# SparkFun_GPS_NEO_M9N_SMA.net
KiCad netlist of a schematic drawn in EAGLE
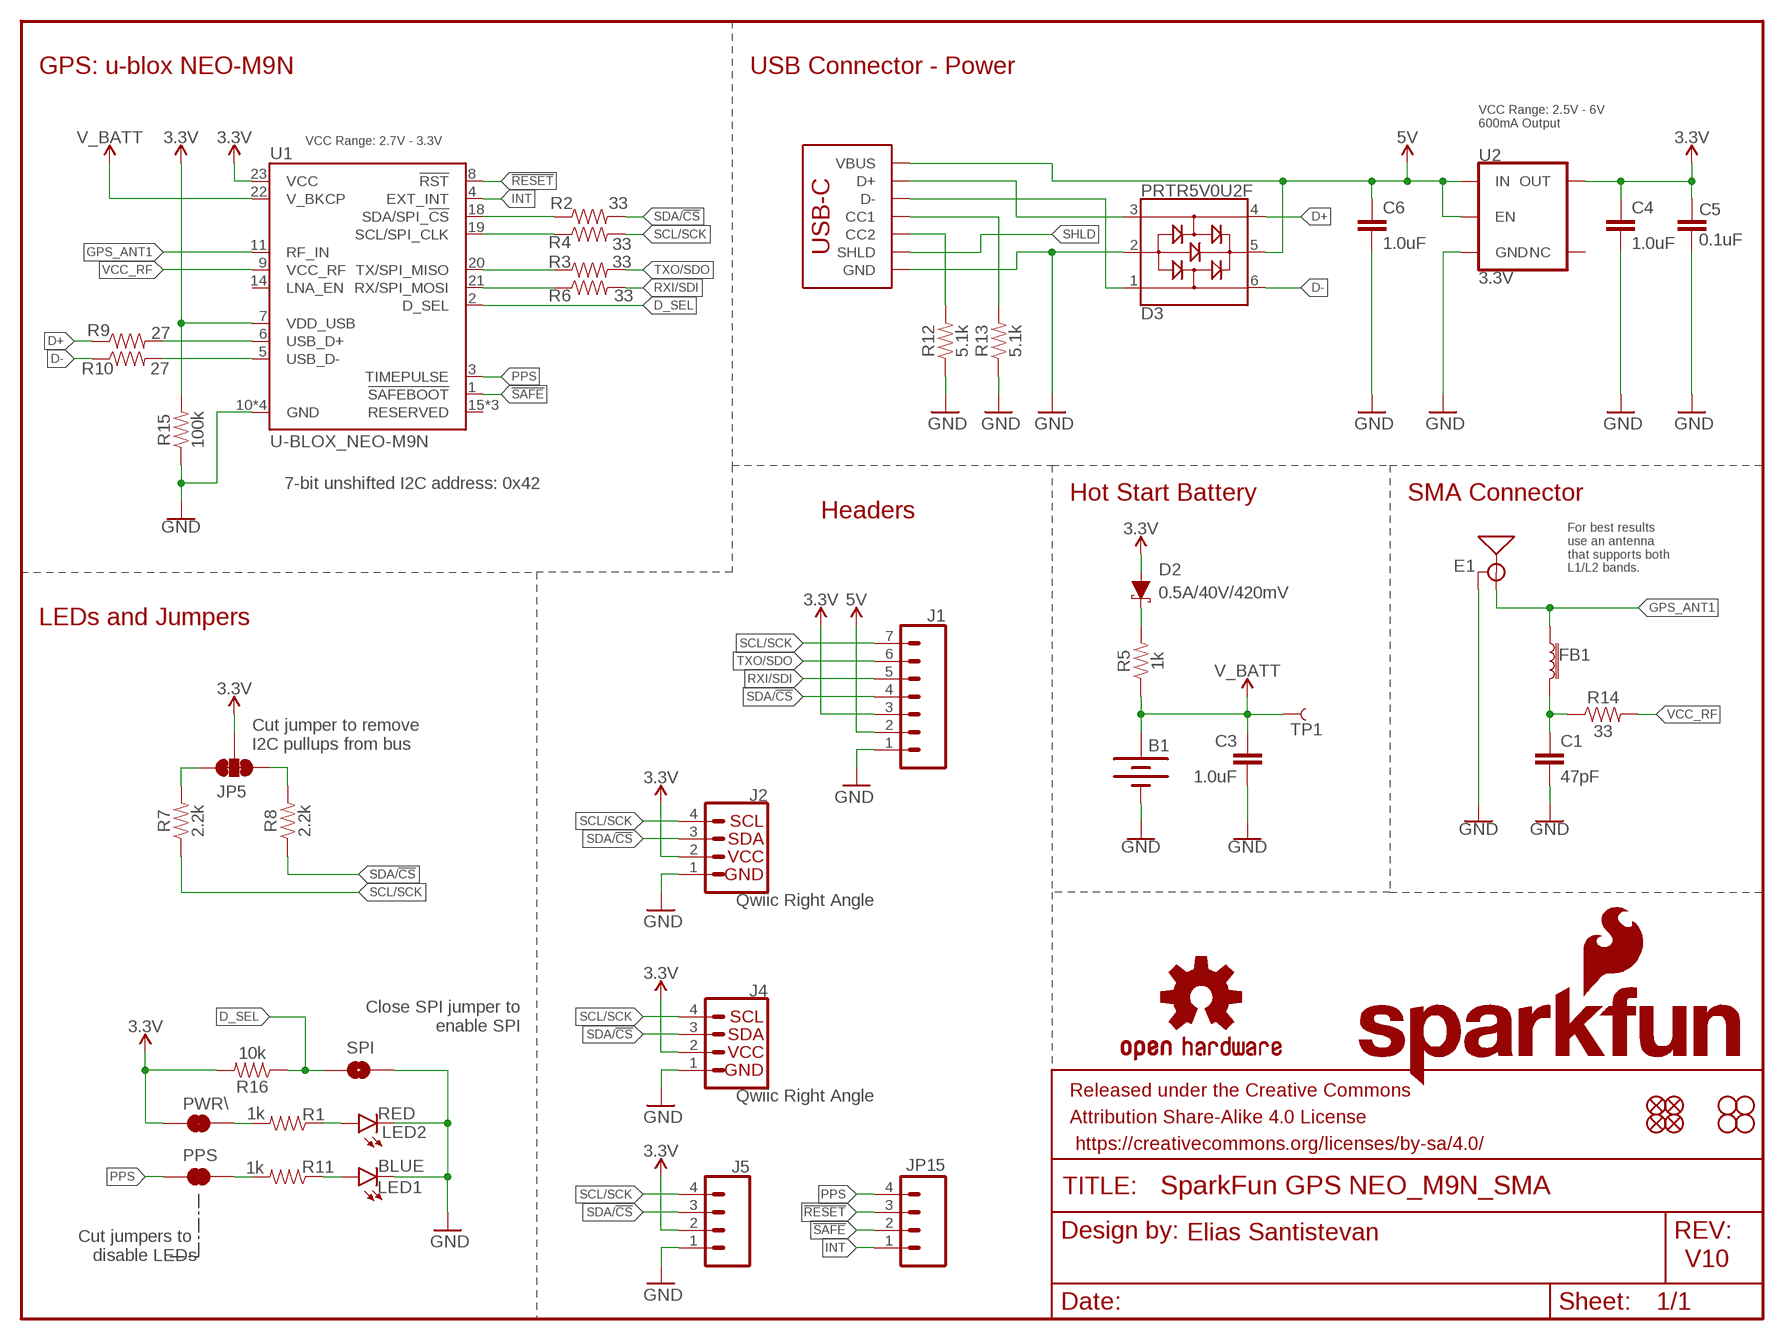
[diagram p0: schematic, sheet 1]

(export (version "E")
  (design (tool "Eeschema 10.0.6"))
  (components
    (comp (ref "B1")
      (value "6.8MM_COIN_CELL")
      (footprint "eagle-import:ML414H_IV01E")
      (libsource (lib "eagle-import") (part "ML414H_IV01E_BATTERY"))
    )
    (comp (ref "C1")
      (value "47pF")
      (footprint "eagle-import:0402")
      (libsource (lib "eagle-import") (part "47PF-0402-25V-5%-X7R"))
    )
    (comp (ref "C3")
      (value "1.0uF")
      (footprint "eagle-import:0603")
      (libsource (lib "eagle-import") (part "1.0UF-0603-16V-10%"))
    )
    (comp (ref "C4")
      (value "1.0uF")
      (footprint "eagle-import:0603")
      (libsource (lib "eagle-import") (part "1.0UF-0603-16V-10%"))
    )
    (comp (ref "C5")
      (value "0.1uF")
      (footprint "eagle-import:0603")
      (libsource (lib "eagle-import") (part "0.1UF-0603-25V-(+80/-20%)"))
    )
    (comp (ref "C6")
      (value "1.0uF")
      (footprint "eagle-import:0603")
      (libsource (lib "eagle-import") (part "1.0UF-0603-16V-10%"))
    )
    (comp (ref "D2")
      (value "0.5A/40V/420mV")
      (footprint "eagle-import:SOD-323")
      (libsource (lib "eagle-import") (part "DIODE-SCHOTTKY-PMEG4005EJ"))
    )
    (comp (ref "D3")
      (value "PRTR5V0U2F")
      (footprint "eagle-import:SOT886")
      (libsource (lib "eagle-import") (part "PRTR5V0U2F"))
    )
    (comp (ref "E1")
      (value "ANTENNA-GROUNDEDEDGE_SMA_SMD")
      (footprint "eagle-import:SMA-EDGE-SMD")
      (libsource (lib "eagle-import") (part "ANTENNA-GROUNDEDEDGE_SMA_SMD"))
    )
    (comp (ref "FB1")
      (value "FERRITE_BEAD-120_OHM-0402")
      (footprint "eagle-import:0402")
      (fields (field (name "MFG_PART") "BLM15HB121SN1D"))
      (libsource (lib "eagle-import") (part "FERRITE_BEAD-120_OHM-0402"))
    )
    (comp (ref "FRAME1")
      (value "FRAME-LETTER")
      (footprint "eagle-import:CREATIVE_COMMONS")
      (libsource (lib "eagle-import") (part "FRAME-LETTER"))
    )
    (comp (ref "J1")
      (value "CONN_07NO_SILK")
      (footprint "eagle-import:1X07_NO_SILK")
      (libsource (lib "eagle-import") (part "CONN_07NO_SILK"))
    )
    (comp (ref "J2")
      (value "Qwiic Right Angle")
      (footprint "eagle-import:JST04_1MM_RA")
      (libsource (lib "eagle-import") (part "I2C_STANDARDQWIIC"))
    )
    (comp (ref "J3")
      (value "USB_C_2-LAYER_PADS")
      (footprint "eagle-import:USB-C-16P-2LAYER-PADS")
      (libsource (lib "eagle-import") (part "USB_C_2-LAYER_PADS"))
    )
    (comp (ref "J4")
      (value "Qwiic Right Angle")
      (footprint "eagle-import:JST04_1MM_RA")
      (libsource (lib "eagle-import") (part "I2C_STANDARDQWIIC"))
    )
    (comp (ref "J5")
      (value "CONN_041X04_NO_SILK_NO_POP")
      (footprint "eagle-import:1X04_NO_SILK")
      (libsource (lib "eagle-import") (part "CONN_041X04_NO_SILK_NO_POP"))
    )
    (comp (ref "JP1")
      (value "STAND-OFF")
      (footprint "eagle-import:STAND-OFF")
      (libsource (lib "eagle-import") (part "STAND-OFF"))
    )
    (comp (ref "JP5")
      (value "JUMPER-SMT_3_2-NC_TRACE_SILK")
      (footprint "eagle-import:SMT-JUMPER_3_2-NC_TRACE_SILK")
      (libsource (lib "eagle-import") (part "JUMPER-SMT_3_2-NC_TRACE_SILK"))
    )
    (comp (ref "JP15")
      (value "CONN_041X04_NO_SILK_NO_POP")
      (footprint "eagle-import:1X04_NO_SILK")
      (libsource (lib "eagle-import") (part "CONN_041X04_NO_SILK_NO_POP"))
    )
    (comp (ref "JP21")
      (value "FIDUCIALUFIDUCIAL")
      (footprint "eagle-import:MICRO-FIDUCIAL")
      (libsource (lib "eagle-import") (part "FIDUCIALUFIDUCIAL"))
    )
    (comp (ref "JP31")
      (value "STAND-OFF")
      (footprint "eagle-import:STAND-OFF")
      (libsource (lib "eagle-import") (part "STAND-OFF"))
    )
    (comp (ref "JP61")
      (value "FIDUCIALUFIDUCIAL")
      (footprint "eagle-import:MICRO-FIDUCIAL")
      (libsource (lib "eagle-import") (part "FIDUCIALUFIDUCIAL"))
    )
    (comp (ref "JP71")
      (value "FIDUCIALUFIDUCIAL")
      (footprint "eagle-import:MICRO-FIDUCIAL")
      (libsource (lib "eagle-import") (part "FIDUCIALUFIDUCIAL"))
    )
    (comp (ref "JP81")
      (value "FIDUCIALUFIDUCIAL")
      (footprint "eagle-import:MICRO-FIDUCIAL")
      (libsource (lib "eagle-import") (part "FIDUCIALUFIDUCIAL"))
    )
    (comp (ref "JP91")
      (value "STAND-OFF")
      (footprint "eagle-import:STAND-OFF")
      (libsource (lib "eagle-import") (part "STAND-OFF"))
    )
    (comp (ref "JP101")
      (value "STAND-OFF")
      (footprint "eagle-import:STAND-OFF")
      (libsource (lib "eagle-import") (part "STAND-OFF"))
    )
    (comp (ref "LED1")
      (value "BLUE")
      (footprint "eagle-import:LED-0603")
      (libsource (lib "eagle-import") (part "LED-BLUE0603"))
    )
    (comp (ref "LED2")
      (value "RED")
      (footprint "eagle-import:LED-0603")
      (libsource (lib "eagle-import") (part "LED-RED0603"))
    )
    (comp (ref "LOGO1")
      (value "OSHW-LOGOMINI")
      (footprint "eagle-import:OSHW-LOGO-MINI")
      (libsource (lib "eagle-import") (part "OSHW-LOGOMINI"))
    )
    (comp (ref "LOGO2")
      (value "SFE_LOGO_NAME_FLAME.1_INCH")
      (footprint "eagle-import:SFE_LOGO_NAME_FLAME_.1")
      (libsource (lib "eagle-import") (part "SFE_LOGO_NAME_FLAME.1_INCH"))
    )
    (comp (ref "PPS")
      (value "JUMPER-SMT_2_NC_TRACE_SILK")
      (footprint "eagle-import:SMT-JUMPER_2_NC_TRACE_SILK")
      (libsource (lib "eagle-import") (part "JUMPER-SMT_2_NC_TRACE_SILK"))
    )
    (comp (ref "PWR\\")
      (value "JUMPER-SMT_2_NC_TRACE_SILK")
      (footprint "eagle-import:SMT-JUMPER_2_NC_TRACE_SILK")
      (libsource (lib "eagle-import") (part "JUMPER-SMT_2_NC_TRACE_SILK"))
    )
    (comp (ref "R1")
      (value "1k")
      (footprint "eagle-import:0603")
      (libsource (lib "eagle-import") (part "1KOHM-0603-1/10W-1%"))
    )
    (comp (ref "R2")
      (value "33")
      (footprint "eagle-import:0603")
      (libsource (lib "eagle-import") (part "33OHM-0603-1/10W-1%"))
    )
    (comp (ref "R3")
      (value "33")
      (footprint "eagle-import:0603")
      (libsource (lib "eagle-import") (part "33OHM-0603-1/10W-1%"))
    )
    (comp (ref "R4")
      (value "33")
      (footprint "eagle-import:0603")
      (libsource (lib "eagle-import") (part "33OHM-0603-1/10W-1%"))
    )
    (comp (ref "R5")
      (value "1k")
      (footprint "eagle-import:0603")
      (libsource (lib "eagle-import") (part "1KOHM-0603-1/10W-1%"))
    )
    (comp (ref "R6")
      (value "33")
      (footprint "eagle-import:0603")
      (libsource (lib "eagle-import") (part "33OHM-0603-1/10W-1%"))
    )
    (comp (ref "R7")
      (value "2.2k")
      (footprint "eagle-import:0603")
      (libsource (lib "eagle-import") (part "2.2KOHM-0603-1/10W-1%"))
    )
    (comp (ref "R8")
      (value "2.2k")
      (footprint "eagle-import:0603")
      (libsource (lib "eagle-import") (part "2.2KOHM-0603-1/10W-1%"))
    )
    (comp (ref "R9")
      (value "27")
      (footprint "eagle-import:0603")
      (libsource (lib "eagle-import") (part "27OHM-0603-1/10W-1%"))
    )
    (comp (ref "R10")
      (value "27")
      (footprint "eagle-import:0603")
      (libsource (lib "eagle-import") (part "27OHM-0603-1/10W-1%"))
    )
    (comp (ref "R11")
      (value "1k")
      (footprint "eagle-import:0603")
      (libsource (lib "eagle-import") (part "1KOHM-0603-1/10W-1%"))
    )
    (comp (ref "R12")
      (value "5.1k")
      (footprint "eagle-import:0603")
      (libsource (lib "eagle-import") (part "5.1KOHM5.1KOHM-0603-1/10W-1%"))
    )
    (comp (ref "R13")
      (value "5.1k")
      (footprint "eagle-import:0603")
      (libsource (lib "eagle-import") (part "5.1KOHM5.1KOHM-0603-1/10W-1%"))
    )
    (comp (ref "R14")
      (value "33")
      (footprint "eagle-import:0402")
      (libsource (lib "eagle-import") (part "33OHM-0402-1/10W-1%"))
    )
    (comp (ref "R15")
      (value "100k")
      (footprint "eagle-import:0603")
      (libsource (lib "eagle-import") (part "100KOHM-0603-1/10W-1%"))
    )
    (comp (ref "R16")
      (value "10k")
      (footprint "eagle-import:0402")
      (libsource (lib "eagle-import") (part "10KOHM-0402-1/16W-1%"))
    )
    (comp (ref "SPI")
      (value "JUMPER-SMT_2_NO_SILK")
      (footprint "eagle-import:SMT-JUMPER_2_NO_SILK")
      (libsource (lib "eagle-import") (part "JUMPER-SMT_2_NO_SILK"))
    )
    (comp (ref "TP1")
      (value "TEST-POINT3X4")
      (footprint "eagle-import:PAD.03X.04")
      (libsource (lib "eagle-import") (part "TEST-POINT3X4"))
    )
    (comp (ref "U1")
      (value "U-BLOX_NEO-M9N")
      (footprint "eagle-import:NEO-M9N_M8T_M8U")
      (libsource (lib "eagle-import") (part "U-BLOX_NEO-M9N"))
    )
    (comp (ref "U2")
      (value "3.3V")
      (footprint "eagle-import:SOT23-5")
      (libsource (lib "eagle-import") (part "V_REG_AP2112K-3.3V"))
    )
  )
  (nets
    (net (code "1") (name "/SDA{slash}~{CS}") (class "Default")
      (node (ref "J1") (pin "4") (pinfunction "4_4") (pintype "passive"))
      (node (ref "J2") (pin "3") (pinfunction "3_3") (pintype "passive"))
      (node (ref "J4") (pin "3") (pinfunction "3_3") (pintype "passive"))
      (node (ref "J5") (pin "3") (pinfunction "3_3") (pintype "passive"))
      (node (ref "R2") (pin "2") (pinfunction "2_2") (pintype "passive"))
      (node (ref "R8") (pin "1") (pinfunction "1_1") (pintype "passive"))
    )
    (net (code "2") (name "/~{RESET}") (class "Default")
      (node (ref "JP15") (pin "3") (pinfunction "3_3") (pintype "passive"))
      (node (ref "U1") (pin "8") (pinfunction "~{RST}_8") (pintype "bidirectional"))
    )
    (net (code "3") (name "/~{SAFE}") (class "Default")
      (node (ref "JP15") (pin "2") (pinfunction "2_2") (pintype "passive"))
      (node (ref "U1") (pin "1") (pinfunction "~{SAFEBOOT}_1") (pintype "bidirectional"))
    )
    (net (code "4") (name "3.3V") (class "Default")
      (node (ref "C4") (pin "1") (pinfunction "1_1") (pintype "passive"))
      (node (ref "C5") (pin "2") (pinfunction "2_2") (pintype "passive"))
      (node (ref "D2") (pin "A") (pinfunction "A_A") (pintype "passive"))
      (node (ref "J1") (pin "3") (pinfunction "3_3") (pintype "passive"))
      (node (ref "J2") (pin "2") (pinfunction "2_2") (pintype "power_in"))
      (node (ref "J4") (pin "2") (pinfunction "2_2") (pintype "power_in"))
      (node (ref "J5") (pin "2") (pinfunction "2_2") (pintype "passive"))
      (node (ref "JP5") (pin "2") (pinfunction "2_2") (pintype "passive"))
      (node (ref "PWR\\") (pin "2") (pinfunction "2_2") (pintype "passive"))
      (node (ref "R15") (pin "2") (pinfunction "2_2") (pintype "passive"))
      (node (ref "R16") (pin "2") (pinfunction "2_2") (pintype "passive"))
      (node (ref "U1") (pin "23") (pinfunction "VCC_23") (pintype "bidirectional"))
      (node (ref "U1") (pin "7") (pinfunction "VDD_USB_7") (pintype "bidirectional"))
      (node (ref "U2") (pin "5") (pinfunction "OUT_5") (pintype "passive"))
    )
    (net (code "5") (name "5V") (class "Default")
      (node (ref "C6") (pin "1") (pinfunction "1_1") (pintype "passive"))
      (node (ref "D3") (pin "5") (pinfunction "5_5") (pintype "bidirectional"))
      (node (ref "J1") (pin "2") (pinfunction "2_2") (pintype "passive"))
      (node (ref "J3") (pin "VBUS1") (pinfunction "VBUS_VBUS1") (pintype "bidirectional"))
      (node (ref "J3") (pin "VBUS2") (pinfunction "VBUS_VBUS2") (pintype "bidirectional"))
      (node (ref "U2") (pin "1") (pinfunction "IN_1") (pintype "input"))
      (node (ref "U2") (pin "3") (pinfunction "EN_3") (pintype "input"))
    )
    (net (code "6") (name "D+") (class "Default")
      (node (ref "D3") (pin "4") (pinfunction "4_4") (pintype "bidirectional"))
      (node (ref "R9") (pin "1") (pinfunction "1_1") (pintype "passive"))
    )
    (net (code "7") (name "D-") (class "Default")
      (node (ref "D3") (pin "6") (pinfunction "6_6") (pintype "bidirectional"))
      (node (ref "R10") (pin "1") (pinfunction "1_1") (pintype "passive"))
    )
    (net (code "8") (name "D_SEL") (class "Default")
      (node (ref "R16") (pin "1") (pinfunction "1_1") (pintype "passive"))
      (node (ref "SPI") (pin "2") (pinfunction "2_2") (pintype "passive"))
      (node (ref "U1") (pin "2") (pinfunction "D_SEL_2") (pintype "bidirectional"))
    )
    (net (code "9") (name "GND") (class "Default")
      (node (ref "B1") (pin "-") (pinfunction "-_-") (pintype "power_in"))
      (node (ref "C1") (pin "2") (pinfunction "2_2") (pintype "passive"))
      (node (ref "C3") (pin "2") (pinfunction "2_2") (pintype "passive"))
      (node (ref "C4") (pin "2") (pinfunction "2_2") (pintype "passive"))
      (node (ref "C5") (pin "1") (pinfunction "1_1") (pintype "passive"))
      (node (ref "C6") (pin "2") (pinfunction "2_2") (pintype "passive"))
      (node (ref "D3") (pin "2") (pinfunction "2_2") (pintype "bidirectional"))
      (node (ref "E1") (pin "GND@0") (pinfunction "GND_GND@0") (pintype "bidirectional"))
      (node (ref "E1") (pin "GND@1") (pinfunction "GND_GND@1") (pintype "bidirectional"))
      (node (ref "J1") (pin "1") (pinfunction "1_1") (pintype "passive"))
      (node (ref "J2") (pin "1") (pinfunction "1_1") (pintype "power_in"))
      (node (ref "J3") (pin "GND") (pinfunction "GND_GND") (pintype "bidirectional"))
      (node (ref "J3") (pin "GND2") (pinfunction "GND_GND2") (pintype "bidirectional"))
      (node (ref "J4") (pin "1") (pinfunction "1_1") (pintype "power_in"))
      (node (ref "J5") (pin "1") (pinfunction "1_1") (pintype "passive"))
      (node (ref "LED1") (pin "C") (pinfunction "C_C") (pintype "passive"))
      (node (ref "LED2") (pin "C") (pinfunction "C_C") (pintype "passive"))
      (node (ref "R12") (pin "1") (pinfunction "1_1") (pintype "passive"))
      (node (ref "R13") (pin "1") (pinfunction "1_1") (pintype "passive"))
      (node (ref "R15") (pin "1") (pinfunction "1_1") (pintype "passive"))
      (node (ref "SPI") (pin "1") (pinfunction "1_1") (pintype "passive"))
      (node (ref "U1") (pin "10") (pinfunction "GND_10") (pintype "bidirectional"))
      (node (ref "U1") (pin "12") (pinfunction "GND_12") (pintype "bidirectional"))
      (node (ref "U1") (pin "13") (pinfunction "GND_13") (pintype "bidirectional"))
      (node (ref "U1") (pin "24") (pinfunction "GND_24") (pintype "bidirectional"))
      (node (ref "U2") (pin "2") (pinfunction "GND_2") (pintype "input"))
    )
    (net (code "10") (name "GPS_ANT1") (class "Default")
      (node (ref "E1") (pin "SIG") (pinfunction "SIGNAL_SIG") (pintype "bidirectional"))
      (node (ref "FB1") (pin "1") (pinfunction "1_1") (pintype "passive"))
      (node (ref "U1") (pin "11") (pinfunction "RF_IN_11") (pintype "bidirectional"))
    )
    (net (code "11") (name "INT") (class "Default")
      (node (ref "JP15") (pin "1") (pinfunction "1_1") (pintype "passive"))
      (node (ref "U1") (pin "4") (pinfunction "EXT_INT_4") (pintype "bidirectional"))
    )
    (net (code "12") (name "Net-(C1-Pad1)") (class "Default")
      (node (ref "C1") (pin "1") (pinfunction "1_1") (pintype "passive"))
      (node (ref "FB1") (pin "2") (pinfunction "2_2") (pintype "passive"))
      (node (ref "R14") (pin "1") (pinfunction "1_1") (pintype "passive"))
    )
    (net (code "13") (name "Net-(D2-PadC)") (class "Default")
      (node (ref "D2") (pin "C") (pinfunction "C_C") (pintype "passive"))
      (node (ref "R5") (pin "2") (pinfunction "2_2") (pintype "passive"))
    )
    (net (code "14") (name "Net-(D3-Pad1)") (class "Default")
      (node (ref "D3") (pin "1") (pinfunction "1_1") (pintype "bidirectional"))
      (node (ref "J3") (pin "A7") (pinfunction "D-_A7") (pintype "bidirectional"))
      (node (ref "J3") (pin "B7") (pinfunction "D-_B7") (pintype "bidirectional"))
    )
    (net (code "15") (name "Net-(D3-Pad3)") (class "Default")
      (node (ref "D3") (pin "3") (pinfunction "3_3") (pintype "bidirectional"))
      (node (ref "J3") (pin "A6") (pinfunction "D+_A6") (pintype "bidirectional"))
      (node (ref "J3") (pin "B6") (pinfunction "D+_B6") (pintype "bidirectional"))
    )
    (net (code "16") (name "Net-(J3-CC1)") (class "Default")
      (node (ref "J3") (pin "A5") (pinfunction "CC1_A5") (pintype "bidirectional"))
      (node (ref "R13") (pin "2") (pinfunction "2_2") (pintype "passive"))
    )
    (net (code "17") (name "Net-(J3-CC2)") (class "Default")
      (node (ref "J3") (pin "B5") (pinfunction "CC2_B5") (pintype "bidirectional"))
      (node (ref "R12") (pin "2") (pinfunction "2_2") (pintype "passive"))
    )
    (net (code "18") (name "Net-(JP5-Pad1)") (class "Default")
      (node (ref "JP5") (pin "1") (pinfunction "1_1") (pintype "passive"))
      (node (ref "R8") (pin "2") (pinfunction "2_2") (pintype "passive"))
    )
    (net (code "19") (name "Net-(JP5-Pad3)") (class "Default")
      (node (ref "JP5") (pin "3") (pinfunction "3_3") (pintype "passive"))
      (node (ref "R7") (pin "2") (pinfunction "2_2") (pintype "passive"))
    )
    (net (code "20") (name "Net-(LED1-PadA)") (class "Default")
      (node (ref "LED1") (pin "A") (pinfunction "A_A") (pintype "passive"))
      (node (ref "R11") (pin "1") (pinfunction "1_1") (pintype "passive"))
    )
    (net (code "21") (name "Net-(LED2-PadA)") (class "Default")
      (node (ref "LED2") (pin "A") (pinfunction "A_A") (pintype "passive"))
      (node (ref "R1") (pin "1") (pinfunction "1_1") (pintype "passive"))
    )
    (net (code "22") (name "Net-(PPS-Pad1)") (class "Default")
      (node (ref "PPS") (pin "1") (pinfunction "1_1") (pintype "passive"))
      (node (ref "R11") (pin "2") (pinfunction "2_2") (pintype "passive"))
    )
    (net (code "23") (name "Net-(PWR\\-Pad1)") (class "Default")
      (node (ref "PWR\\") (pin "1") (pinfunction "1_1") (pintype "passive"))
      (node (ref "R1") (pin "2") (pinfunction "2_2") (pintype "passive"))
    )
    (net (code "24") (name "Net-(U1-RX{slash}SPI_MOSI)") (class "Default")
      (node (ref "R6") (pin "1") (pinfunction "1_1") (pintype "passive"))
      (node (ref "U1") (pin "21") (pinfunction "RX/SPI_MOSI_21") (pintype "bidirectional"))
    )
    (net (code "25") (name "Net-(U1-SCL{slash}SPI_CLK)") (class "Default")
      (node (ref "R4") (pin "1") (pinfunction "1_1") (pintype "passive"))
      (node (ref "U1") (pin "19") (pinfunction "SCL/SPI_CLK_19") (pintype "bidirectional"))
    )
    (net (code "26") (name "Net-(U1-SDA{slash}SPI_~{CS})") (class "Default")
      (node (ref "R2") (pin "1") (pinfunction "1_1") (pintype "passive"))
      (node (ref "U1") (pin "18") (pinfunction "SDA/SPI_~{CS}_18") (pintype "bidirectional"))
    )
    (net (code "27") (name "Net-(U1-TX{slash}SPI_MISO)") (class "Default")
      (node (ref "R3") (pin "1") (pinfunction "1_1") (pintype "passive"))
      (node (ref "U1") (pin "20") (pinfunction "TX/SPI_MISO_20") (pintype "bidirectional"))
    )
    (net (code "28") (name "Net-(U1-USB_D+)") (class "Default")
      (node (ref "R9") (pin "2") (pinfunction "2_2") (pintype "passive"))
      (node (ref "U1") (pin "6") (pinfunction "USB_D+_6") (pintype "bidirectional"))
    )
    (net (code "29") (name "Net-(U1-USB_D-)") (class "Default")
      (node (ref "R10") (pin "2") (pinfunction "2_2") (pintype "passive"))
      (node (ref "U1") (pin "5") (pinfunction "USB_D-_5") (pintype "bidirectional"))
    )
    (net (code "30") (name "PPS") (class "Default")
      (node (ref "JP15") (pin "4") (pinfunction "4_4") (pintype "passive"))
      (node (ref "PPS") (pin "2") (pinfunction "2_2") (pintype "passive"))
      (node (ref "U1") (pin "3") (pinfunction "TIMEPULSE_3") (pintype "bidirectional"))
    )
    (net (code "31") (name "RXI{slash}SDI") (class "Default")
      (node (ref "J1") (pin "5") (pinfunction "5_5") (pintype "passive"))
      (node (ref "R6") (pin "2") (pinfunction "2_2") (pintype "passive"))
    )
    (net (code "32") (name "SCL{slash}SCK") (class "Default")
      (node (ref "J1") (pin "7") (pinfunction "7_7") (pintype "passive"))
      (node (ref "J2") (pin "4") (pinfunction "4_4") (pintype "passive"))
      (node (ref "J4") (pin "4") (pinfunction "4_4") (pintype "passive"))
      (node (ref "J5") (pin "4") (pinfunction "4_4") (pintype "passive"))
      (node (ref "R4") (pin "2") (pinfunction "2_2") (pintype "passive"))
      (node (ref "R7") (pin "1") (pinfunction "1_1") (pintype "passive"))
    )
    (net (code "33") (name "SHLD") (class "Default")
      (node (ref "J3") (pin "SHLD1") (pinfunction "SHLD_SHLD1") (pintype "bidirectional"))
      (node (ref "J3") (pin "SHLD2") (pinfunction "SHLD_SHLD2") (pintype "bidirectional"))
      (node (ref "J3") (pin "SHLD3") (pinfunction "SHLD_SHLD3") (pintype "bidirectional"))
      (node (ref "J3") (pin "SHLD4") (pinfunction "SHLD_SHLD4") (pintype "bidirectional"))
    )
    (net (code "34") (name "TXO{slash}SDO") (class "Default")
      (node (ref "J1") (pin "6") (pinfunction "6_6") (pintype "passive"))
      (node (ref "R3") (pin "2") (pinfunction "2_2") (pintype "passive"))
    )
    (net (code "35") (name "VCC_RF") (class "Default")
      (node (ref "R14") (pin "2") (pinfunction "2_2") (pintype "passive"))
      (node (ref "U1") (pin "9") (pinfunction "VCC_RF_9") (pintype "bidirectional"))
    )
    (net (code "36") (name "V_BATT") (class "Default")
      (node (ref "B1") (pin "+") (pinfunction "+_+") (pintype "power_in"))
      (node (ref "C3") (pin "1") (pinfunction "1_1") (pintype "passive"))
      (node (ref "R5") (pin "1") (pinfunction "1_1") (pintype "passive"))
      (node (ref "TP1") (pin "P$1") (pinfunction "1_P$1") (pintype "bidirectional"))
      (node (ref "U1") (pin "22") (pinfunction "V_BKCP_22") (pintype "bidirectional"))
    )
    (net (code "37") (name "unconnected-(U1-LNA_EN-Pad14)") (class "Default")
      (node (ref "U1") (pin "14") (pinfunction "LNA_EN_14") (pintype "bidirectional"))
    )
    (net (code "38") (name "unconnected-(U1-RESERVED-Pad15)") (class "Default")
      (node (ref "U1") (pin "15") (pinfunction "RESERVED_15") (pintype "no_connect"))
    )
    (net (code "39") (name "unconnected-(U1-RESERVED-Pad16)") (class "Default")
      (node (ref "U1") (pin "16") (pinfunction "RESERVED_16") (pintype "no_connect"))
    )
    (net (code "40") (name "unconnected-(U1-RESERVED-Pad17)") (class "Default")
      (node (ref "U1") (pin "17") (pinfunction "RESERVED_17") (pintype "no_connect"))
    )
    (net (code "41") (name "unconnected-(U2-NC-Pad4)") (class "Default")
      (node (ref "U2") (pin "4") (pinfunction "NC_4") (pintype "no_connect"))
    )
  )
)
